# Digital_Input.net
KiCad netlist of a schematic drawn in Altium Designer
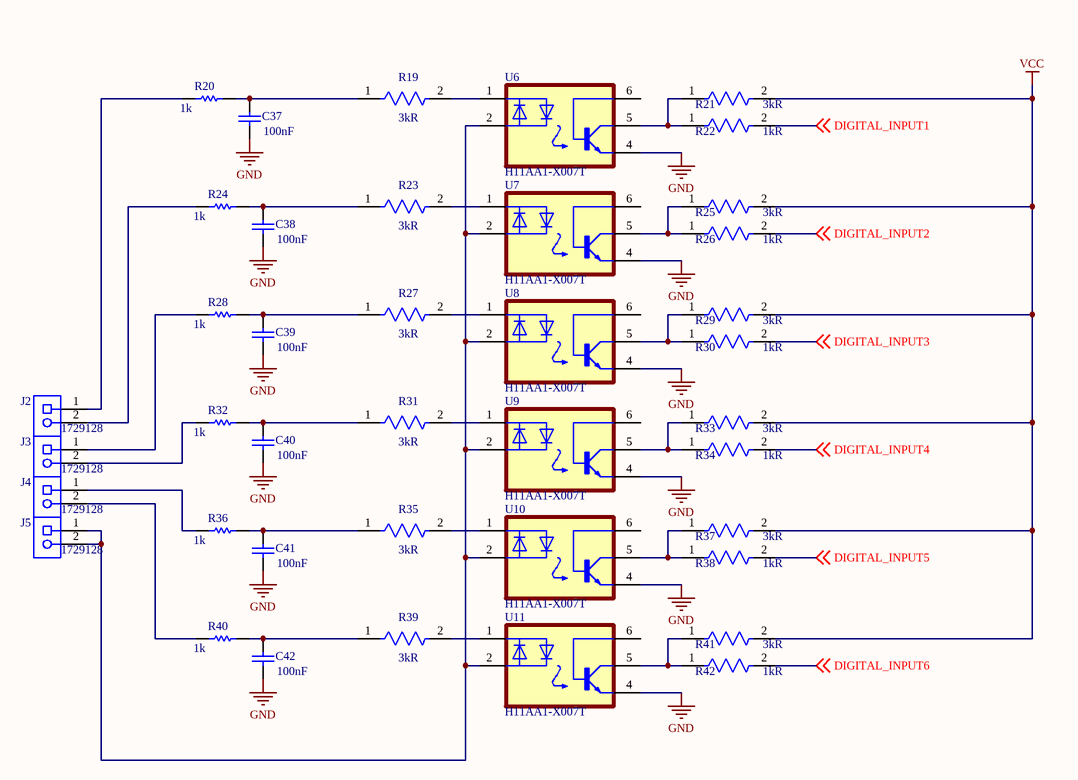
[diagram p0: Digital_Input.SchDoc]

(export (version "E")
  (design (tool "Eeschema 10.0.6"))
  (components
    (comp (ref "C37")
      (value "100nF")
      (footprint "CAPC1608X87X35NL15T15")
      (fields (field (name "MANUFACTURER") "Kemet") (field (name "PART NUMBER") "C0603T104K3RACTU"))
      (libsource (lib "Altium Content Vault") (part "CAP"))
    )
    (comp (ref "C38")
      (value "100nF")
      (footprint "CAPC1608X87X35NL15T15")
      (fields (field (name "MANUFACTURER") "Kemet") (field (name "PART NUMBER") "C0603T104K3RACTU"))
      (libsource (lib "Altium Content Vault") (part "CAP"))
    )
    (comp (ref "C39")
      (value "100nF")
      (footprint "CAPC1608X87X35NL15T15")
      (fields (field (name "MANUFACTURER") "Kemet") (field (name "PART NUMBER") "C0603T104K3RACTU"))
      (libsource (lib "Altium Content Vault") (part "CAP"))
    )
    (comp (ref "C40")
      (value "100nF")
      (footprint "CAPC1608X87X35NL15T15")
      (fields (field (name "MANUFACTURER") "Kemet") (field (name "PART NUMBER") "C0603T104K3RACTU"))
      (libsource (lib "Altium Content Vault") (part "CAP"))
    )
    (comp (ref "C41")
      (value "100nF")
      (footprint "CAPC1608X87X35NL15T15")
      (fields (field (name "MANUFACTURER") "Kemet") (field (name "PART NUMBER") "C0603T104K3RACTU"))
      (libsource (lib "Altium Content Vault") (part "CAP"))
    )
    (comp (ref "C42")
      (value "100nF")
      (footprint "CAPC1608X87X35NL15T15")
      (fields (field (name "MANUFACTURER") "Kemet") (field (name "PART NUMBER") "C0603T104K3RACTU"))
      (libsource (lib "Altium Content Vault") (part "CAP"))
    )
    (comp (ref "J2")
      (value "1729128")
      (footprint "PHOE-1729128-2_V")
      (description "PCB Terminal Block, 13.5 A, 400 V, 2-Pin THD, RoHS, Bulk")
      (fields (field (name "MANUFACTURER") "Phoenix Contact"))
      (libsource (lib "Altium Content Vault") (part "CN-2P-F-R2"))
    )
    (comp (ref "J3")
      (value "1729128")
      (footprint "PHOE-1729128-2_V")
      (description "PCB Terminal Block, 13.5 A, 400 V, 2-Pin THD, RoHS, Bulk")
      (fields (field (name "MANUFACTURER") "Phoenix Contact"))
      (libsource (lib "Altium Content Vault") (part "CN-2P-F-R2"))
    )
    (comp (ref "J4")
      (value "1729128")
      (footprint "PHOE-1729128-2_V")
      (description "PCB Terminal Block, 13.5 A, 400 V, 2-Pin THD, RoHS, Bulk")
      (fields (field (name "MANUFACTURER") "Phoenix Contact"))
      (libsource (lib "Altium Content Vault") (part "CN-2P-F-R2"))
    )
    (comp (ref "J5")
      (value "1729128")
      (footprint "PHOE-1729128-2_V")
      (description "PCB Terminal Block, 13.5 A, 400 V, 2-Pin THD, RoHS, Bulk")
      (fields (field (name "MANUFACTURER") "Phoenix Contact"))
      (libsource (lib "Altium Content Vault") (part "CN-2P-F-R2"))
    )
    (comp (ref "R19")
      (value "CRCW06033K00FKEA")
      (footprint "FP-CRCW0603-e3-IPC_A")
      (description "RES Thick Film, 3kΩ, 1%, 0.1W, 100ppm/°C, 0603")
      (fields (field (name "RESISTANCE") "3kR") (field (name "TOLERANCE") "1%"))
      (libsource (lib "Altium Content Vault") (part "1029c3af85768c4190bb7ad29bc67b5"))
    )
    (comp (ref "R20")
      (value "1k")
      (footprint "RESC1608X55X25LL10T15")
      (fields (field (name "PART NUMBER") "RT0603DRE071KL") (field (name "MANUFACTURER") "Yageo"))
      (libsource (lib "Altium Content Vault") (part "RES"))
    )
    (comp (ref "R21")
      (value "CRCW06033K00FKEA")
      (footprint "FP-CRCW0603-e3-IPC_A")
      (description "RES Thick Film, 3kΩ, 1%, 0.1W, 100ppm/°C, 0603")
      (fields (field (name "RESISTANCE") "3kR") (field (name "TOLERANCE") "1%"))
      (libsource (lib "Altium Content Vault") (part "1029c3af85768c4190bb7ad29bc67b5"))
    )
    (comp (ref "R22")
      (value "RC0603FR-071KL")
      (footprint "FP-RC0603-0_55-IPC_C")
      (description "RES 1K OHM 1% 1/10W 0603")
      (fields (field (name "RESISTANCE") "1kR") (field (name "TOLERANCE") "1%"))
      (libsource (lib "Altium Content Vault") (part "1029c3af85768c4190bb7ad29bc67b5"))
    )
    (comp (ref "R23")
      (value "CRCW06033K00FKEA")
      (footprint "FP-CRCW0603-e3-IPC_A")
      (description "RES Thick Film, 3kΩ, 1%, 0.1W, 100ppm/°C, 0603")
      (fields (field (name "RESISTANCE") "3kR") (field (name "TOLERANCE") "1%"))
      (libsource (lib "Altium Content Vault") (part "1029c3af85768c4190bb7ad29bc67b5"))
    )
    (comp (ref "R24")
      (value "1k")
      (footprint "RESC1608X55X25LL10T15")
      (fields (field (name "PART NUMBER") "RT0603DRE071KL") (field (name "MANUFACTURER") "Yageo"))
      (libsource (lib "Altium Content Vault") (part "RES"))
    )
    (comp (ref "R25")
      (value "CRCW06033K00FKEA")
      (footprint "FP-CRCW0603-e3-IPC_A")
      (description "RES Thick Film, 3kΩ, 1%, 0.1W, 100ppm/°C, 0603")
      (fields (field (name "RESISTANCE") "3kR") (field (name "TOLERANCE") "1%"))
      (libsource (lib "Altium Content Vault") (part "1029c3af85768c4190bb7ad29bc67b5"))
    )
    (comp (ref "R26")
      (value "RC0603FR-071KL")
      (footprint "FP-RC0603-0_55-IPC_C")
      (description "RES 1K OHM 1% 1/10W 0603")
      (fields (field (name "RESISTANCE") "1kR") (field (name "TOLERANCE") "1%"))
      (libsource (lib "Altium Content Vault") (part "1029c3af85768c4190bb7ad29bc67b5"))
    )
    (comp (ref "R27")
      (value "CRCW06033K00FKEA")
      (footprint "FP-CRCW0603-e3-IPC_A")
      (description "RES Thick Film, 3kΩ, 1%, 0.1W, 100ppm/°C, 0603")
      (fields (field (name "RESISTANCE") "3kR") (field (name "TOLERANCE") "1%"))
      (libsource (lib "Altium Content Vault") (part "1029c3af85768c4190bb7ad29bc67b5"))
    )
    (comp (ref "R28")
      (value "1k")
      (footprint "RESC1608X55X25LL10T15")
      (fields (field (name "PART NUMBER") "RT0603DRE071KL") (field (name "MANUFACTURER") "Yageo"))
      (libsource (lib "Altium Content Vault") (part "RES"))
    )
    (comp (ref "R29")
      (value "CRCW06033K00FKEA")
      (footprint "FP-CRCW0603-e3-IPC_A")
      (description "RES Thick Film, 3kΩ, 1%, 0.1W, 100ppm/°C, 0603")
      (fields (field (name "RESISTANCE") "3kR") (field (name "TOLERANCE") "1%"))
      (libsource (lib "Altium Content Vault") (part "1029c3af85768c4190bb7ad29bc67b5"))
    )
    (comp (ref "R30")
      (value "RC0603FR-071KL")
      (footprint "FP-RC0603-0_55-IPC_C")
      (description "RES 1K OHM 1% 1/10W 0603")
      (fields (field (name "RESISTANCE") "1kR") (field (name "TOLERANCE") "1%"))
      (libsource (lib "Altium Content Vault") (part "1029c3af85768c4190bb7ad29bc67b5"))
    )
    (comp (ref "R31")
      (value "CRCW06033K00FKEA")
      (footprint "FP-CRCW0603-e3-IPC_A")
      (description "RES Thick Film, 3kΩ, 1%, 0.1W, 100ppm/°C, 0603")
      (fields (field (name "RESISTANCE") "3kR") (field (name "TOLERANCE") "1%"))
      (libsource (lib "Altium Content Vault") (part "1029c3af85768c4190bb7ad29bc67b5"))
    )
    (comp (ref "R32")
      (value "1k")
      (footprint "RESC1608X55X25LL10T15")
      (fields (field (name "PART NUMBER") "RT0603DRE071KL") (field (name "MANUFACTURER") "Yageo"))
      (libsource (lib "Altium Content Vault") (part "RES"))
    )
    (comp (ref "R33")
      (value "CRCW06033K00FKEA")
      (footprint "FP-CRCW0603-e3-IPC_A")
      (description "RES Thick Film, 3kΩ, 1%, 0.1W, 100ppm/°C, 0603")
      (fields (field (name "RESISTANCE") "3kR") (field (name "TOLERANCE") "1%"))
      (libsource (lib "Altium Content Vault") (part "1029c3af85768c4190bb7ad29bc67b5"))
    )
    (comp (ref "R34")
      (value "RC0603FR-071KL")
      (footprint "FP-RC0603-0_55-IPC_C")
      (description "RES 1K OHM 1% 1/10W 0603")
      (fields (field (name "RESISTANCE") "1kR") (field (name "TOLERANCE") "1%"))
      (libsource (lib "Altium Content Vault") (part "1029c3af85768c4190bb7ad29bc67b5"))
    )
    (comp (ref "R35")
      (value "CRCW06033K00FKEA")
      (footprint "FP-CRCW0603-e3-IPC_A")
      (description "RES Thick Film, 3kΩ, 1%, 0.1W, 100ppm/°C, 0603")
      (fields (field (name "RESISTANCE") "3kR") (field (name "TOLERANCE") "1%"))
      (libsource (lib "Altium Content Vault") (part "1029c3af85768c4190bb7ad29bc67b5"))
    )
    (comp (ref "R36")
      (value "1k")
      (footprint "RESC1608X55X25LL10T15")
      (fields (field (name "PART NUMBER") "RT0603DRE071KL") (field (name "MANUFACTURER") "Yageo"))
      (libsource (lib "Altium Content Vault") (part "RES"))
    )
    (comp (ref "R37")
      (value "CRCW06033K00FKEA")
      (footprint "FP-CRCW0603-e3-IPC_A")
      (description "RES Thick Film, 3kΩ, 1%, 0.1W, 100ppm/°C, 0603")
      (fields (field (name "RESISTANCE") "3kR") (field (name "TOLERANCE") "1%"))
      (libsource (lib "Altium Content Vault") (part "1029c3af85768c4190bb7ad29bc67b5"))
    )
    (comp (ref "R38")
      (value "RC0603FR-071KL")
      (footprint "FP-RC0603-0_55-IPC_C")
      (description "RES 1K OHM 1% 1/10W 0603")
      (fields (field (name "RESISTANCE") "1kR") (field (name "TOLERANCE") "1%"))
      (libsource (lib "Altium Content Vault") (part "1029c3af85768c4190bb7ad29bc67b5"))
    )
    (comp (ref "R39")
      (value "CRCW06033K00FKEA")
      (footprint "FP-CRCW0603-e3-IPC_A")
      (description "RES Thick Film, 3kΩ, 1%, 0.1W, 100ppm/°C, 0603")
      (fields (field (name "RESISTANCE") "3kR") (field (name "TOLERANCE") "1%"))
      (libsource (lib "Altium Content Vault") (part "1029c3af85768c4190bb7ad29bc67b5"))
    )
    (comp (ref "R40")
      (value "1k")
      (footprint "RESC1608X55X25LL10T15")
      (fields (field (name "PART NUMBER") "RT0603DRE071KL") (field (name "MANUFACTURER") "Yageo"))
      (libsource (lib "Altium Content Vault") (part "RES"))
    )
    (comp (ref "R41")
      (value "CRCW06033K00FKEA")
      (footprint "FP-CRCW0603-e3-IPC_A")
      (description "RES Thick Film, 3kΩ, 1%, 0.1W, 100ppm/°C, 0603")
      (fields (field (name "RESISTANCE") "3kR") (field (name "TOLERANCE") "1%"))
      (libsource (lib "Altium Content Vault") (part "1029c3af85768c4190bb7ad29bc67b5"))
    )
    (comp (ref "R42")
      (value "RC0603FR-071KL")
      (footprint "FP-RC0603-0_55-IPC_C")
      (description "RES 1K OHM 1% 1/10W 0603")
      (fields (field (name "RESISTANCE") "1kR") (field (name "TOLERANCE") "1%"))
      (libsource (lib "Altium Content Vault") (part "1029c3af85768c4190bb7ad29bc67b5"))
    )
    (comp (ref "U6")
      (value "H11AA1-X007T")
      (footprint "SOIC254P1030X460-6N")
      (description "H11AA1 Series Single Channel 30V 5300 Vrms SMT Phototransistor Optocoupler DIP-6")
      (fields (field (name "MF") "Vishay Semiconductor"))
      (libsource (lib "H11AA1-X007T") (part "H11AA1-X007T"))
    )
    (comp (ref "U7")
      (value "H11AA1-X007T")
      (footprint "SOIC254P1030X460-6N")
      (description "H11AA1 Series Single Channel 30V 5300 Vrms SMT Phototransistor Optocoupler DIP-6")
      (fields (field (name "MF") "Vishay Semiconductor"))
      (libsource (lib "H11AA1-X007T") (part "H11AA1-X007T"))
    )
    (comp (ref "U8")
      (value "H11AA1-X007T")
      (footprint "SOIC254P1030X460-6N")
      (description "H11AA1 Series Single Channel 30V 5300 Vrms SMT Phototransistor Optocoupler DIP-6")
      (fields (field (name "MF") "Vishay Semiconductor"))
      (libsource (lib "H11AA1-X007T") (part "H11AA1-X007T"))
    )
    (comp (ref "U9")
      (value "H11AA1-X007T")
      (footprint "SOIC254P1030X460-6N")
      (description "H11AA1 Series Single Channel 30V 5300 Vrms SMT Phototransistor Optocoupler DIP-6")
      (fields (field (name "MF") "Vishay Semiconductor"))
      (libsource (lib "H11AA1-X007T") (part "H11AA1-X007T"))
    )
    (comp (ref "U10")
      (value "H11AA1-X007T")
      (footprint "SOIC254P1030X460-6N")
      (description "H11AA1 Series Single Channel 30V 5300 Vrms SMT Phototransistor Optocoupler DIP-6")
      (fields (field (name "MF") "Vishay Semiconductor"))
      (libsource (lib "H11AA1-X007T") (part "H11AA1-X007T"))
    )
    (comp (ref "U11")
      (value "H11AA1-X007T")
      (footprint "SOIC254P1030X460-6N")
      (description "H11AA1 Series Single Channel 30V 5300 Vrms SMT Phototransistor Optocoupler DIP-6")
      (fields (field (name "MF") "Vishay Semiconductor"))
      (libsource (lib "H11AA1-X007T") (part "H11AA1-X007T"))
    )
  )
  (nets
    (net (code "1") (name "DIGITAL_INPUT1") (class "Default")
      (node (ref "R22") (pin "2") (pinfunction "2_2") (pintype "passive"))
    )
    (net (code "2") (name "DIGITAL_INPUT2") (class "Default")
      (node (ref "R26") (pin "2") (pinfunction "2_2") (pintype "passive"))
    )
    (net (code "3") (name "DIGITAL_INPUT3") (class "Default")
      (node (ref "R30") (pin "2") (pinfunction "2_2") (pintype "passive"))
    )
    (net (code "4") (name "DIGITAL_INPUT4") (class "Default")
      (node (ref "R34") (pin "2") (pinfunction "2_2") (pintype "passive"))
    )
    (net (code "5") (name "DIGITAL_INPUT5") (class "Default")
      (node (ref "R38") (pin "2") (pinfunction "2_2") (pintype "passive"))
    )
    (net (code "6") (name "DIGITAL_INPUT6") (class "Default")
      (node (ref "R42") (pin "2") (pinfunction "2_2") (pintype "passive"))
    )
    (net (code "7") (name "GND") (class "Default")
      (node (ref "C37") (pin "1") (pinfunction "1_1") (pintype "passive"))
      (node (ref "C38") (pin "1") (pinfunction "1_1") (pintype "passive"))
      (node (ref "C39") (pin "1") (pinfunction "1_1") (pintype "passive"))
      (node (ref "C40") (pin "1") (pinfunction "1_1") (pintype "passive"))
      (node (ref "C41") (pin "1") (pinfunction "1_1") (pintype "passive"))
      (node (ref "C42") (pin "1") (pinfunction "1_1") (pintype "passive"))
      (node (ref "U10") (pin "4") (pinfunction "E_4") (pintype "passive"))
      (node (ref "U11") (pin "4") (pinfunction "E_4") (pintype "passive"))
      (node (ref "U6") (pin "4") (pinfunction "E_4") (pintype "passive"))
      (node (ref "U7") (pin "4") (pinfunction "E_4") (pintype "passive"))
      (node (ref "U8") (pin "4") (pinfunction "E_4") (pintype "passive"))
      (node (ref "U9") (pin "4") (pinfunction "E_4") (pintype "passive"))
    )
    (net (code "8") (name "Net-(C37-Pad2)") (class "Default")
      (node (ref "C37") (pin "2") (pinfunction "2_2") (pintype "passive"))
      (node (ref "R19") (pin "1") (pinfunction "1_1") (pintype "passive"))
      (node (ref "R20") (pin "2") (pinfunction "2_2") (pintype "passive"))
    )
    (net (code "9") (name "Net-(C38-Pad2)") (class "Default")
      (node (ref "C38") (pin "2") (pinfunction "2_2") (pintype "passive"))
      (node (ref "R23") (pin "1") (pinfunction "1_1") (pintype "passive"))
      (node (ref "R24") (pin "2") (pinfunction "2_2") (pintype "passive"))
    )
    (net (code "10") (name "Net-(C39-Pad2)") (class "Default")
      (node (ref "C39") (pin "2") (pinfunction "2_2") (pintype "passive"))
      (node (ref "R27") (pin "1") (pinfunction "1_1") (pintype "passive"))
      (node (ref "R28") (pin "2") (pinfunction "2_2") (pintype "passive"))
    )
    (net (code "11") (name "Net-(C40-Pad2)") (class "Default")
      (node (ref "C40") (pin "2") (pinfunction "2_2") (pintype "passive"))
      (node (ref "R31") (pin "1") (pinfunction "1_1") (pintype "passive"))
      (node (ref "R32") (pin "2") (pinfunction "2_2") (pintype "passive"))
    )
    (net (code "12") (name "Net-(C41-Pad2)") (class "Default")
      (node (ref "C41") (pin "2") (pinfunction "2_2") (pintype "passive"))
      (node (ref "R35") (pin "1") (pinfunction "1_1") (pintype "passive"))
      (node (ref "R36") (pin "2") (pinfunction "2_2") (pintype "passive"))
    )
    (net (code "13") (name "Net-(C42-Pad2)") (class "Default")
      (node (ref "C42") (pin "2") (pinfunction "2_2") (pintype "passive"))
      (node (ref "R39") (pin "1") (pinfunction "1_1") (pintype "passive"))
      (node (ref "R40") (pin "2") (pinfunction "2_2") (pintype "passive"))
    )
    (net (code "14") (name "Net-(J2-Pad1)") (class "Default")
      (node (ref "J2") (pin "1") (pinfunction "1_1") (pintype "passive"))
      (node (ref "R20") (pin "1") (pinfunction "1_1") (pintype "passive"))
    )
    (net (code "15") (name "Net-(J2-Pad2)") (class "Default")
      (node (ref "J2") (pin "2") (pinfunction "2_2") (pintype "passive"))
      (node (ref "R24") (pin "1") (pinfunction "1_1") (pintype "passive"))
    )
    (net (code "16") (name "Net-(J3-Pad1)") (class "Default")
      (node (ref "J3") (pin "1") (pinfunction "1_1") (pintype "passive"))
      (node (ref "R28") (pin "1") (pinfunction "1_1") (pintype "passive"))
    )
    (net (code "17") (name "Net-(J3-Pad2)") (class "Default")
      (node (ref "J3") (pin "2") (pinfunction "2_2") (pintype "passive"))
      (node (ref "R32") (pin "1") (pinfunction "1_1") (pintype "passive"))
    )
    (net (code "18") (name "Net-(J4-Pad1)") (class "Default")
      (node (ref "J4") (pin "1") (pinfunction "1_1") (pintype "passive"))
      (node (ref "R36") (pin "1") (pinfunction "1_1") (pintype "passive"))
    )
    (net (code "19") (name "Net-(J4-Pad2)") (class "Default")
      (node (ref "J4") (pin "2") (pinfunction "2_2") (pintype "passive"))
      (node (ref "R40") (pin "1") (pinfunction "1_1") (pintype "passive"))
    )
    (net (code "20") (name "Net-(U6-A{slash}C)") (class "Default")
      (node (ref "R19") (pin "2") (pinfunction "2_2") (pintype "passive"))
      (node (ref "U6") (pin "1") (pinfunction "A/C_1") (pintype "passive"))
    )
    (net (code "21") (name "Net-(U6-C)") (class "Default")
      (node (ref "R21") (pin "1") (pinfunction "1_1") (pintype "passive"))
      (node (ref "R22") (pin "1") (pinfunction "1_1") (pintype "passive"))
      (node (ref "U6") (pin "5") (pinfunction "C_5") (pintype "passive"))
    )
    (net (code "22") (name "Net-(U7-A{slash}C)") (class "Default")
      (node (ref "R23") (pin "2") (pinfunction "2_2") (pintype "passive"))
      (node (ref "U7") (pin "1") (pinfunction "A/C_1") (pintype "passive"))
    )
    (net (code "23") (name "Net-(U7-C)") (class "Default")
      (node (ref "R25") (pin "1") (pinfunction "1_1") (pintype "passive"))
      (node (ref "R26") (pin "1") (pinfunction "1_1") (pintype "passive"))
      (node (ref "U7") (pin "5") (pinfunction "C_5") (pintype "passive"))
    )
    (net (code "24") (name "Net-(U8-A{slash}C)") (class "Default")
      (node (ref "R27") (pin "2") (pinfunction "2_2") (pintype "passive"))
      (node (ref "U8") (pin "1") (pinfunction "A/C_1") (pintype "passive"))
    )
    (net (code "25") (name "Net-(U8-C)") (class "Default")
      (node (ref "R29") (pin "1") (pinfunction "1_1") (pintype "passive"))
      (node (ref "R30") (pin "1") (pinfunction "1_1") (pintype "passive"))
      (node (ref "U8") (pin "5") (pinfunction "C_5") (pintype "passive"))
    )
    (net (code "26") (name "Net-(U9-A{slash}C)") (class "Default")
      (node (ref "R31") (pin "2") (pinfunction "2_2") (pintype "passive"))
      (node (ref "U9") (pin "1") (pinfunction "A/C_1") (pintype "passive"))
    )
    (net (code "27") (name "Net-(U9-C)") (class "Default")
      (node (ref "R33") (pin "1") (pinfunction "1_1") (pintype "passive"))
      (node (ref "R34") (pin "1") (pinfunction "1_1") (pintype "passive"))
      (node (ref "U9") (pin "5") (pinfunction "C_5") (pintype "passive"))
    )
    (net (code "28") (name "Net-(U10-A{slash}C)") (class "Default")
      (node (ref "R35") (pin "2") (pinfunction "2_2") (pintype "passive"))
      (node (ref "U10") (pin "1") (pinfunction "A/C_1") (pintype "passive"))
    )
    (net (code "29") (name "Net-(U10-C)") (class "Default")
      (node (ref "R37") (pin "1") (pinfunction "1_1") (pintype "passive"))
      (node (ref "R38") (pin "1") (pinfunction "1_1") (pintype "passive"))
      (node (ref "U10") (pin "5") (pinfunction "C_5") (pintype "passive"))
    )
    (net (code "30") (name "Net-(U10-C{slash}A)") (class "Default")
      (node (ref "J5") (pin "1") (pinfunction "1_1") (pintype "passive"))
      (node (ref "J5") (pin "2") (pinfunction "2_2") (pintype "passive"))
      (node (ref "U10") (pin "2") (pinfunction "C/A_2") (pintype "passive"))
      (node (ref "U11") (pin "2") (pinfunction "C/A_2") (pintype "passive"))
      (node (ref "U6") (pin "2") (pinfunction "C/A_2") (pintype "passive"))
      (node (ref "U7") (pin "2") (pinfunction "C/A_2") (pintype "passive"))
      (node (ref "U8") (pin "2") (pinfunction "C/A_2") (pintype "passive"))
      (node (ref "U9") (pin "2") (pinfunction "C/A_2") (pintype "passive"))
    )
    (net (code "31") (name "Net-(U11-A{slash}C)") (class "Default")
      (node (ref "R39") (pin "2") (pinfunction "2_2") (pintype "passive"))
      (node (ref "U11") (pin "1") (pinfunction "A/C_1") (pintype "passive"))
    )
    (net (code "32") (name "Net-(U11-C)") (class "Default")
      (node (ref "R41") (pin "1") (pinfunction "1_1") (pintype "passive"))
      (node (ref "R42") (pin "1") (pinfunction "1_1") (pintype "passive"))
      (node (ref "U11") (pin "5") (pinfunction "C_5") (pintype "passive"))
    )
    (net (code "33") (name "VCC") (class "Default")
      (node (ref "R21") (pin "2") (pinfunction "2_2") (pintype "passive"))
      (node (ref "R25") (pin "2") (pinfunction "2_2") (pintype "passive"))
      (node (ref "R29") (pin "2") (pinfunction "2_2") (pintype "passive"))
      (node (ref "R33") (pin "2") (pinfunction "2_2") (pintype "passive"))
      (node (ref "R37") (pin "2") (pinfunction "2_2") (pintype "passive"))
      (node (ref "R41") (pin "2") (pinfunction "2_2") (pintype "passive"))
    )
    (net (code "34") (name "unconnected-(U6-B-Pad6)") (class "Default")
      (node (ref "U6") (pin "6") (pinfunction "B_6") (pintype "passive"))
    )
    (net (code "35") (name "unconnected-(U7-B-Pad6)") (class "Default")
      (node (ref "U7") (pin "6") (pinfunction "B_6") (pintype "passive"))
    )
    (net (code "36") (name "unconnected-(U8-B-Pad6)") (class "Default")
      (node (ref "U8") (pin "6") (pinfunction "B_6") (pintype "passive"))
    )
    (net (code "37") (name "unconnected-(U9-B-Pad6)") (class "Default")
      (node (ref "U9") (pin "6") (pinfunction "B_6") (pintype "passive"))
    )
    (net (code "38") (name "unconnected-(U10-B-Pad6)") (class "Default")
      (node (ref "U10") (pin "6") (pinfunction "B_6") (pintype "passive"))
    )
    (net (code "39") (name "unconnected-(U11-B-Pad6)") (class "Default")
      (node (ref "U11") (pin "6") (pinfunction "B_6") (pintype "passive"))
    )
  )
)
